# LPCB227_-_I2C_EXTENDER.net
KiCad netlist of a schematic drawn in Altium Designer
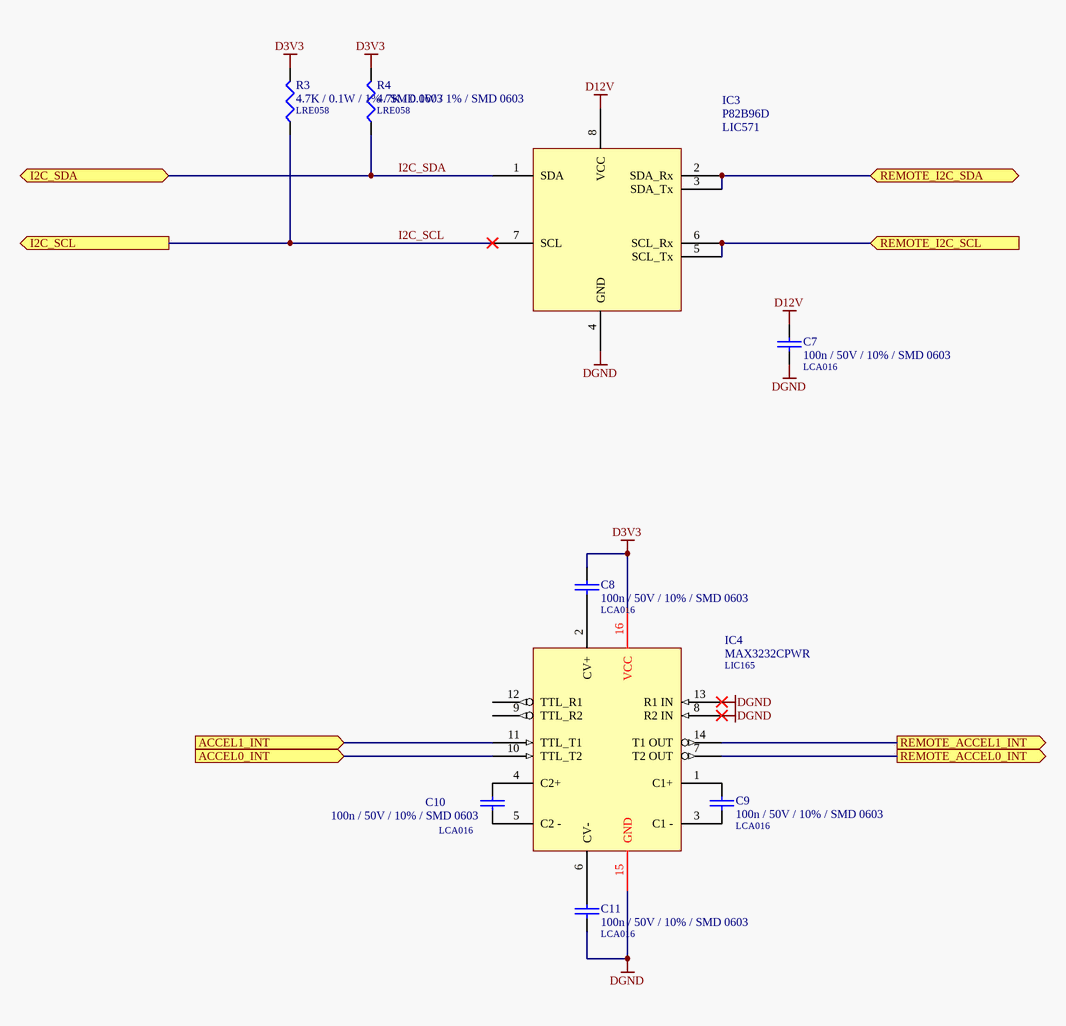
[diagram p0: LPCB227 - I2C EXTENDER.SchDoc]

(export (version "E")
  (design (tool "Eeschema 10.0.6"))
  (components
    (comp (ref "C7")
      (value "100n / 50V / 10% / SMD 0603")
      (footprint "LFP011__CC1608-0603-IPC7351_B")
      (description "Capacitor, Ceramic Chip, 100nF (0.1uF), 50V, 5%, SMD 0603 [LCA016]")
      (fields (field (name "LDL_NUMBER") "LCA016"))
      (libsource (lib "LDL_Capacitors") (part "100n / 50V / 10% / SMD 0603"))
    )
    (comp (ref "C8")
      (value "100n / 50V / 10% / SMD 0603")
      (footprint "LFP011__CC1608-0603-IPC7351_B")
      (description "Capacitor, Ceramic Chip, 100nF, 50V, 10%, SMD 0603")
      (fields (field (name "LDL_NUMBER") "LCA016"))
      (libsource (lib "LDL_Capacitors") (part "100n / 50V / 10% / SMD 0603"))
    )
    (comp (ref "C9")
      (value "100n / 50V / 10% / SMD 0603")
      (footprint "LFP011__CC1608-0603-IPC7351_B")
      (description "Capacitor, Ceramic Chip, 100nF, 50V, 10%, SMD 0603")
      (fields (field (name "LDL_NUMBER") "LCA016"))
      (libsource (lib "LDL_Capacitors") (part "100n / 50V / 10% / SMD 0603"))
    )
    (comp (ref "C10")
      (value "100n / 50V / 10% / SMD 0603")
      (footprint "LFP011__CC1608-0603-IPC7351_B")
      (description "Capacitor, Ceramic Chip, 100nF, 50V, 10%, SMD 0603")
      (fields (field (name "LDL_NUMBER") "LCA016"))
      (libsource (lib "LDL_Capacitors") (part "100n / 50V / 10% / SMD 0603"))
    )
    (comp (ref "C11")
      (value "100n / 50V / 10% / SMD 0603")
      (footprint "LFP011__CC1608-0603-IPC7351_B")
      (description "Capacitor, Ceramic Chip, 100nF, 50V, 10%, SMD 0603")
      (fields (field (name "LDL_NUMBER") "LCA016"))
      (libsource (lib "LDL_Capacitors") (part "100n / 50V / 10% / SMD 0603"))
    )
    (comp (ref "IC3")
      (value "P82B96D")
      (footprint "LFP097__SOIC150-8")
      (description "IC, I2C Line Driver [LIC571]")
      (fields (field (name "LDL_NUMBER") "LIC571"))
      (libsource (lib "LDL_Semiconductors") (part "P82B96D"))
    )
    (comp (ref "IC4")
      (value "MAX3232CPWR")
      (footprint "LFP049__TSSOP-16")
      (description "IC, RS232 Line Driver, 3.3V, SMD TSSOP16")
      (fields (field (name "LDL_NUMBER") "LIC165"))
      (libsource (lib "LDL_Semiconductors") (part "MAX3232CPWR"))
    )
    (comp (ref "R3")
      (value "4.7K / 0.1W / 1% / SMD 0603")
      (footprint "LFP020__CR1608-0603-IPC7351_B")
      (description "Resistor, Ceramic Chip, 4K7, 0.1W, 1%, SMD 0603 [LRE058]")
      (fields (field (name "LDL_NUMBER") "LRE058"))
      (libsource (lib "LDL_Resistors") (part "4.7K / 0.1W / 1% / SMD 0603"))
    )
    (comp (ref "R4")
      (value "4.7K / 0.1W / 1% / SMD 0603")
      (footprint "LFP020__CR1608-0603-IPC7351_B")
      (description "Resistor, Ceramic Chip, 4K7, 0.1W, 1%, SMD 0603 [LRE058]")
      (fields (field (name "LDL_NUMBER") "LRE058"))
      (libsource (lib "LDL_Resistors") (part "4.7K / 0.1W / 1% / SMD 0603"))
    )
  )
  (nets
    (net (code "1") (name "/ACCEL0_INT") (class "Default")
      (node (ref "IC4") (pin "10") (pinfunction "TTL_T2_10") (pintype "input"))
    )
    (net (code "2") (name "/ACCEL1_INT") (class "Default")
      (node (ref "IC4") (pin "11") (pinfunction "TTL_T1_11") (pintype "input"))
    )
    (net (code "3") (name "/I2C_SCL") (class "Default")
      (node (ref "IC3") (pin "7") (pinfunction "SCL_7") (pintype "passive"))
      (node (ref "R3") (pin "1") (pintype "passive"))
    )
    (net (code "4") (name "/I2C_SDA") (class "Default")
      (node (ref "IC3") (pin "1") (pinfunction "SDA_1") (pintype "passive"))
      (node (ref "R4") (pin "1") (pintype "passive"))
    )
    (net (code "5") (name "/REMOTE_ACCEL0_INT") (class "Default")
      (node (ref "IC4") (pin "7") (pinfunction "T2_OUT_7") (pintype "output"))
    )
    (net (code "6") (name "/REMOTE_ACCEL1_INT") (class "Default")
      (node (ref "IC4") (pin "14") (pinfunction "T1_OUT_14") (pintype "output"))
    )
    (net (code "7") (name "/REMOTE_I2C_SCL") (class "Default")
      (node (ref "IC3") (pin "5") (pinfunction "SCL_Tx_5") (pintype "passive"))
      (node (ref "IC3") (pin "6") (pinfunction "SCL_Rx_6") (pintype "passive"))
    )
    (net (code "8") (name "/REMOTE_I2C_SDA") (class "Default")
      (node (ref "IC3") (pin "2") (pinfunction "SDA_Rx_2") (pintype "passive"))
      (node (ref "IC3") (pin "3") (pinfunction "SDA_Tx_3") (pintype "passive"))
    )
    (net (code "9") (name "D3V3") (class "Default")
      (node (ref "C8") (pin "1") (pintype "passive"))
      (node (ref "IC4") (pin "16") (pinfunction "VCC_16") (pintype "power_in"))
      (node (ref "R3") (pin "2") (pintype "passive"))
      (node (ref "R4") (pin "2") (pintype "passive"))
    )
    (net (code "10") (name "D12V") (class "Default")
      (node (ref "C7") (pin "1") (pintype "passive"))
      (node (ref "IC3") (pin "8") (pinfunction "VCC_8") (pintype "power_in"))
    )
    (net (code "11") (name "DGND") (class "Default")
      (node (ref "C11") (pin "2") (pintype "passive"))
      (node (ref "C7") (pin "2") (pintype "passive"))
      (node (ref "IC3") (pin "4") (pinfunction "GND_4") (pintype "power_in"))
      (node (ref "IC4") (pin "13") (pinfunction "R1_IN_13") (pintype "input"))
      (node (ref "IC4") (pin "15") (pinfunction "GND_15") (pintype "power_in"))
      (node (ref "IC4") (pin "8") (pinfunction "R2_IN_8") (pintype "input"))
    )
    (net (code "12") (name "Net-(IC4-C1+)") (class "Default")
      (node (ref "C9") (pin "1") (pintype "passive"))
      (node (ref "IC4") (pin "1") (pinfunction "C1+_1") (pintype "passive"))
    )
    (net (code "13") (name "Net-(IC4-C1_-)") (class "Default")
      (node (ref "C9") (pin "2") (pintype "passive"))
      (node (ref "IC4") (pin "3") (pinfunction "C1_-_3") (pintype "passive"))
    )
    (net (code "14") (name "Net-(IC4-C2+)") (class "Default")
      (node (ref "C10") (pin "1") (pintype "passive"))
      (node (ref "IC4") (pin "4") (pinfunction "C2+_4") (pintype "passive"))
    )
    (net (code "15") (name "Net-(IC4-C2_-)") (class "Default")
      (node (ref "C10") (pin "2") (pintype "passive"))
      (node (ref "IC4") (pin "5") (pinfunction "C2_-_5") (pintype "passive"))
    )
    (net (code "16") (name "Net-(IC4-CV+)") (class "Default")
      (node (ref "C8") (pin "2") (pintype "passive"))
      (node (ref "IC4") (pin "2") (pinfunction "CV+_2") (pintype "passive"))
    )
    (net (code "17") (name "Net-(IC4-CV-)") (class "Default")
      (node (ref "C11") (pin "1") (pintype "passive"))
      (node (ref "IC4") (pin "6") (pinfunction "CV-_6") (pintype "passive"))
    )
    (net (code "18") (name "unconnected-(IC4-TTL_R1-Pad12)") (class "Default")
      (node (ref "IC4") (pin "12") (pinfunction "TTL_R1_12") (pintype "output"))
    )
    (net (code "19") (name "unconnected-(IC4-TTL_R2-Pad9)") (class "Default")
      (node (ref "IC4") (pin "9") (pinfunction "TTL_R2_9") (pintype "output"))
    )
  )
)
